# LAB03_2020-11-16_16-58-59.net
KiCad netlist of a schematic drawn in EasyEDA
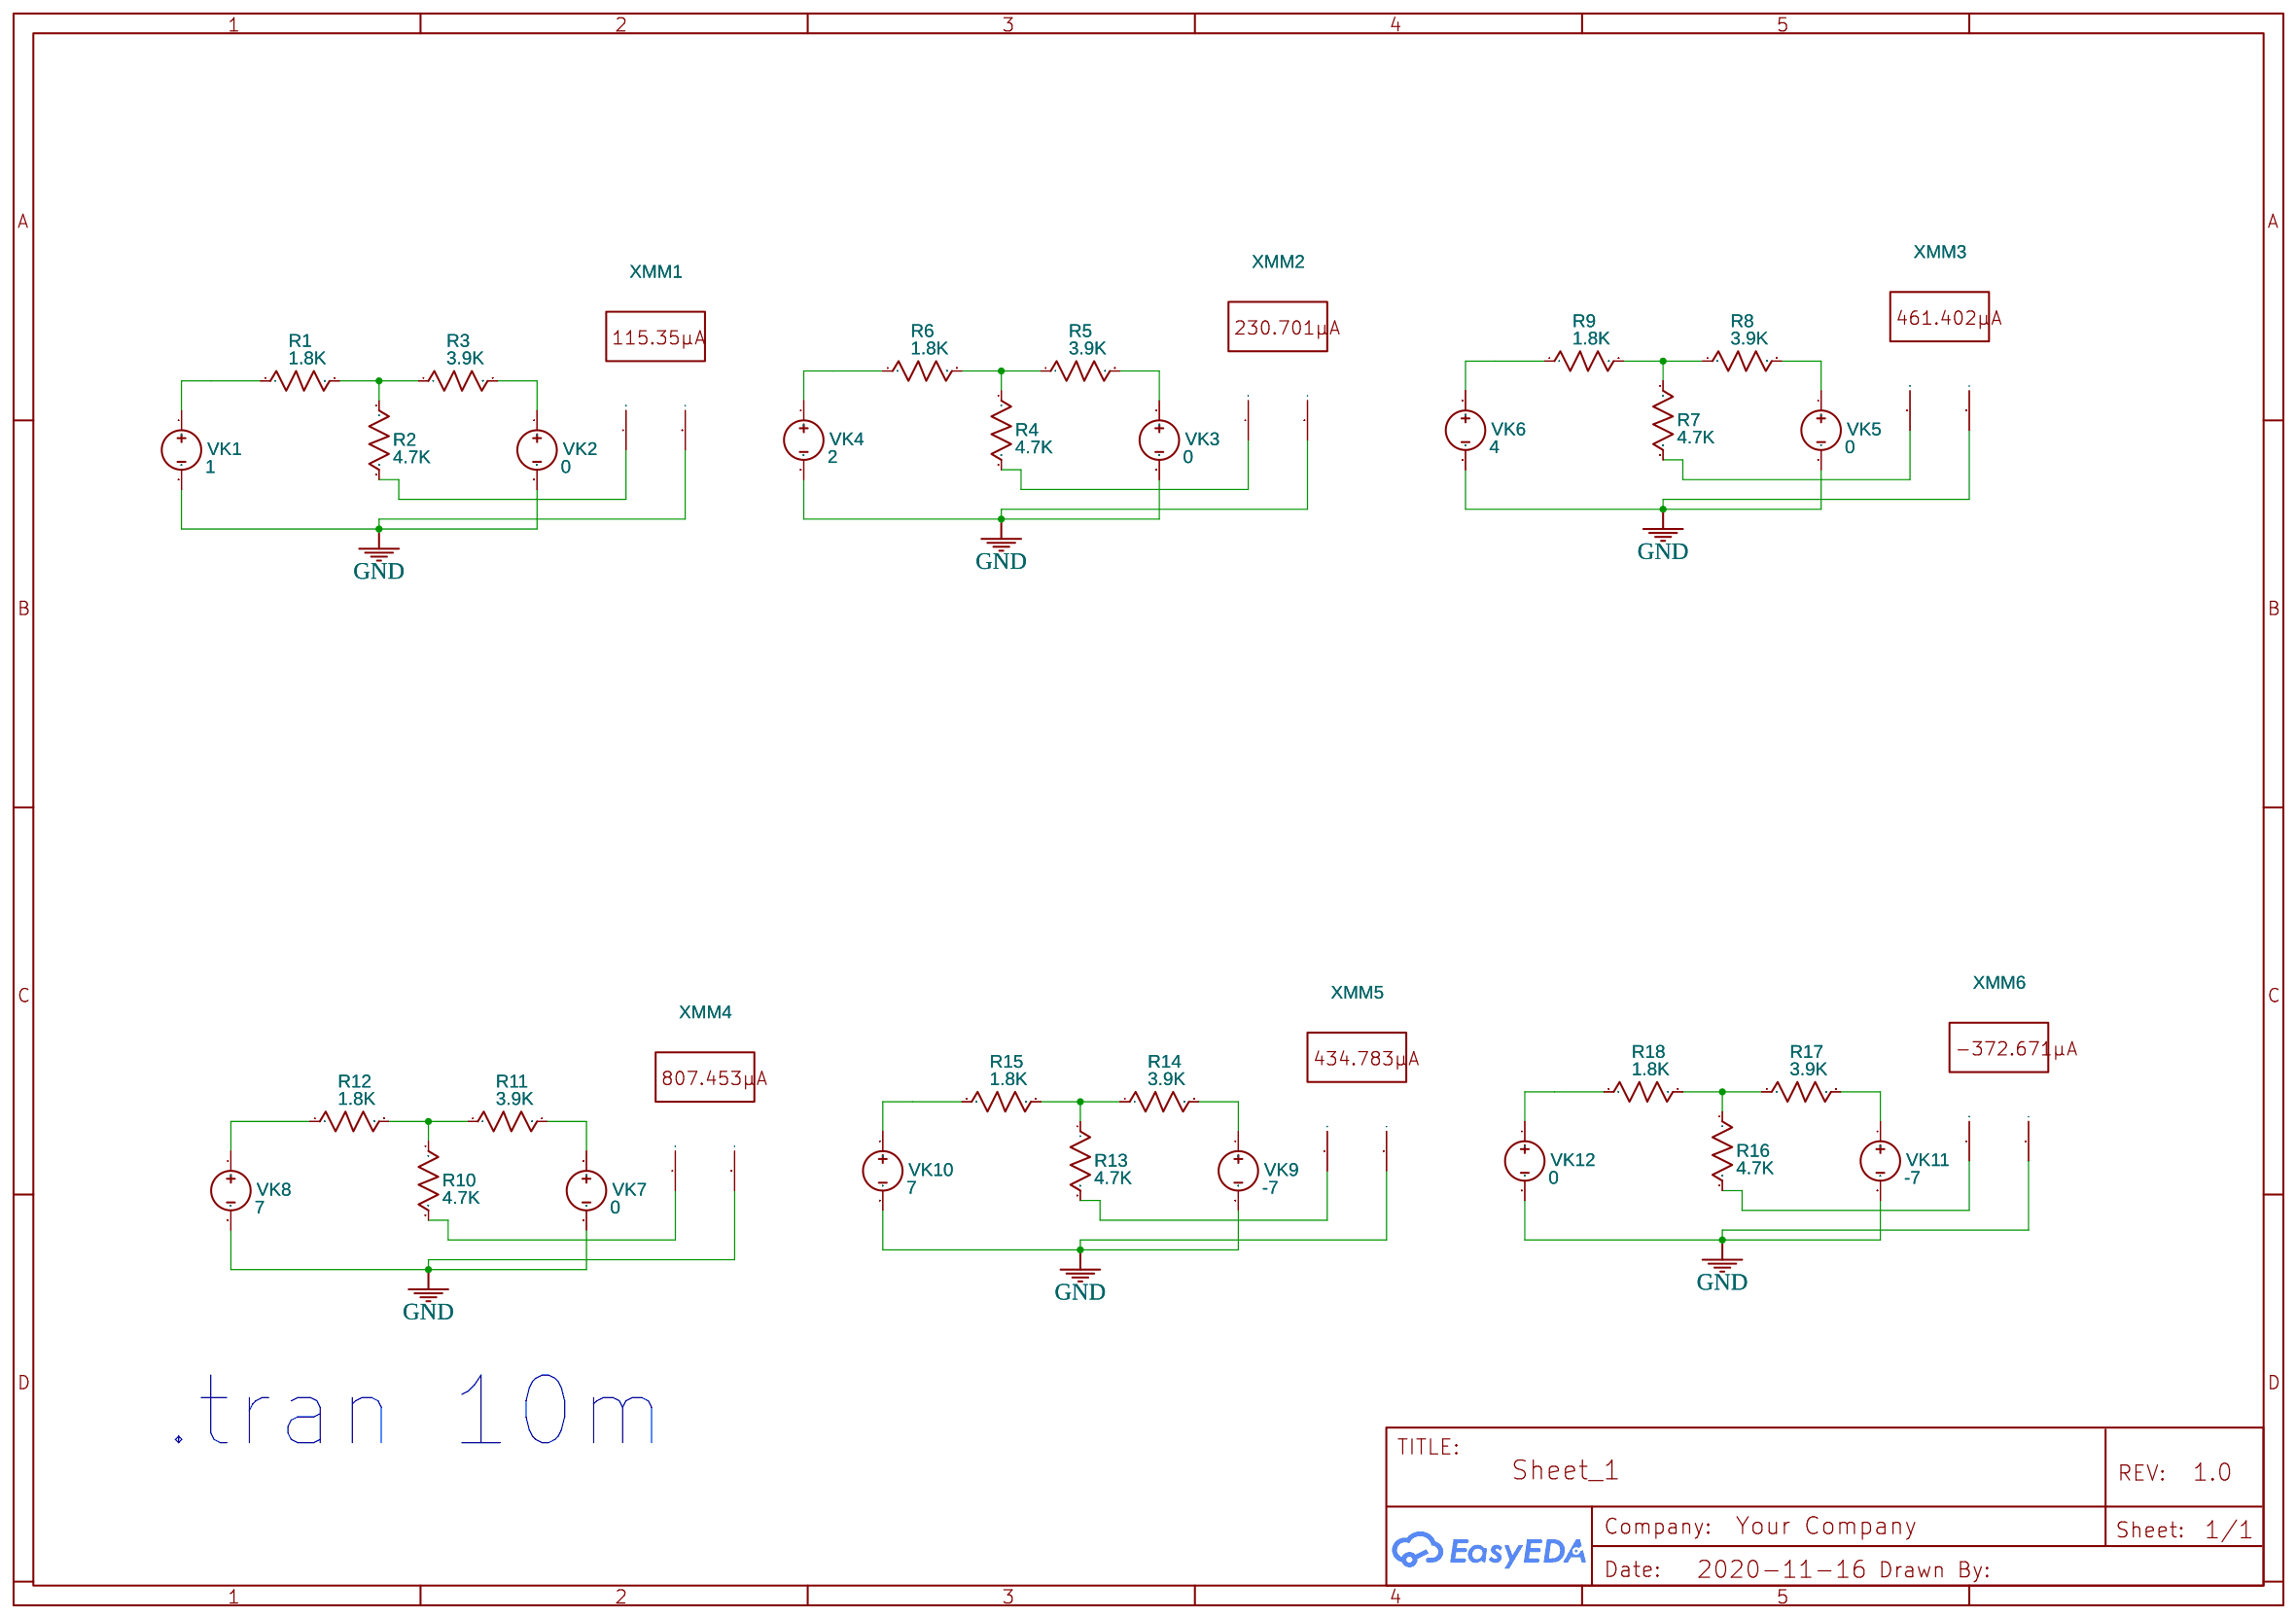
[diagram p0: schematic sheet]

(export (version "E")
  (design (tool "Eeschema 10.0.6"))
  (components
    (comp (ref "R1") (value "1.8K") (libsource (lib "") (part "Resistor_US_1")))
    (comp (ref "R2") (value "4.7K") (libsource (lib "") (part "Resistor_US")))
    (comp (ref "R3") (value "3.9K") (libsource (lib "") (part "Resistor_US_1")))
    (comp (ref "R4") (value "4.7K") (libsource (lib "") (part "Resistor_US")))
    (comp (ref "R5") (value "3.9K") (libsource (lib "") (part "Resistor_US_1")))
    (comp (ref "R6") (value "1.8K") (libsource (lib "") (part "Resistor_US_1")))
    (comp (ref "R7") (value "4.7K") (libsource (lib "") (part "Resistor_US")))
    (comp (ref "R8") (value "3.9K") (libsource (lib "") (part "Resistor_US_1")))
    (comp (ref "R9") (value "1.8K") (libsource (lib "") (part "Resistor_US_1")))
    (comp (ref "R10") (value "4.7K") (libsource (lib "") (part "Resistor_US")))
    (comp (ref "R11") (value "3.9K") (libsource (lib "") (part "Resistor_US_1")))
    (comp (ref "R12") (value "1.8K") (libsource (lib "") (part "Resistor_US_1")))
    (comp (ref "R13") (value "4.7K") (libsource (lib "") (part "Resistor_US")))
    (comp (ref "R14") (value "3.9K") (libsource (lib "") (part "Resistor_US_1")))
    (comp (ref "R15") (value "1.8K") (libsource (lib "") (part "Resistor_US_1")))
    (comp (ref "R16") (value "4.7K") (libsource (lib "") (part "Resistor_US")))
    (comp (ref "R17") (value "3.9K") (libsource (lib "") (part "Resistor_US_1")))
    (comp (ref "R18") (value "1.8K") (libsource (lib "") (part "Resistor_US_1")))
    (comp (ref "VK1") (value "1") (libsource (lib "") (part "VDC")))
    (comp (ref "VK2") (value "0") (libsource (lib "") (part "VDC")))
    (comp (ref "VK3") (value "0") (libsource (lib "") (part "VDC")))
    (comp (ref "VK4") (value "2") (libsource (lib "") (part "VDC")))
    (comp (ref "VK5") (value "0") (libsource (lib "") (part "VDC")))
    (comp (ref "VK6") (value "4") (libsource (lib "") (part "VDC")))
    (comp (ref "VK7") (value "0") (libsource (lib "") (part "VDC")))
    (comp (ref "VK8") (value "7") (libsource (lib "") (part "VDC")))
    (comp (ref "VK9") (value "-7") (libsource (lib "") (part "VDC")))
    (comp (ref "VK10") (value "7") (libsource (lib "") (part "VDC")))
    (comp (ref "VK11") (value "-7") (libsource (lib "") (part "VDC")))
    (comp (ref "VK12") (value "0") (libsource (lib "") (part "VDC")))
    (comp (ref "XMM1") (value "Multimeter") (libsource (lib "") (part "MULTIMETER_2")))
    (comp (ref "XMM2") (value "Multimeter") (libsource (lib "") (part "MULTIMETER_5")))
    (comp (ref "XMM3") (value "Multimeter") (libsource (lib "") (part "MULTIMETER_1")))
    (comp (ref "XMM4") (value "Multimeter") (libsource (lib "") (part "MULTIMETER_3")))
    (comp (ref "XMM5") (value "Multimeter") (libsource (lib "") (part "MULTIMETER")))
    (comp (ref "XMM6") (value "Multimeter") (libsource (lib "") (part "MULTIMETER_4")))
  )
  (nets
    (net (code "1") (name "GND") (class "Default")
      (node (ref "VK1") (pin "2") (pinfunction "2_2") (pintype "unspecified"))
      (node (ref "VK10") (pin "2") (pinfunction "2_2") (pintype "unspecified"))
      (node (ref "VK11") (pin "2") (pinfunction "2_2") (pintype "unspecified"))
      (node (ref "VK12") (pin "2") (pinfunction "2_2") (pintype "unspecified"))
      (node (ref "VK2") (pin "2") (pinfunction "2_2") (pintype "unspecified"))
      (node (ref "VK3") (pin "2") (pinfunction "2_2") (pintype "unspecified"))
      (node (ref "VK4") (pin "2") (pinfunction "2_2") (pintype "unspecified"))
      (node (ref "VK5") (pin "2") (pinfunction "2_2") (pintype "unspecified"))
      (node (ref "VK6") (pin "2") (pinfunction "2_2") (pintype "unspecified"))
      (node (ref "VK7") (pin "2") (pinfunction "2_2") (pintype "unspecified"))
      (node (ref "VK8") (pin "2") (pinfunction "2_2") (pintype "unspecified"))
      (node (ref "VK9") (pin "2") (pinfunction "2_2") (pintype "unspecified"))
      (node (ref "XMM1") (pin "2") (pinfunction "I_2") (pintype "unspecified"))
      (node (ref "XMM2") (pin "2") (pinfunction "I_2") (pintype "unspecified"))
      (node (ref "XMM3") (pin "2") (pinfunction "I_2") (pintype "unspecified"))
      (node (ref "XMM4") (pin "2") (pinfunction "I_2") (pintype "unspecified"))
      (node (ref "XMM5") (pin "2") (pinfunction "I_2") (pintype "unspecified"))
      (node (ref "XMM6") (pin "2") (pinfunction "I_2") (pintype "unspecified"))
    )
    (net (code "2") (name "Net-(R1-Pad1)") (class "Default")
      (node (ref "R1") (pin "1") (pinfunction "1_1") (pintype "unspecified"))
      (node (ref "VK1") (pin "1") (pinfunction "1_1") (pintype "unspecified"))
    )
    (net (code "3") (name "Net-(R1-Pad2)") (class "Default")
      (node (ref "R1") (pin "2") (pinfunction "2_2") (pintype "unspecified"))
      (node (ref "R2") (pin "1") (pinfunction "1_1") (pintype "unspecified"))
      (node (ref "R3") (pin "1") (pinfunction "1_1") (pintype "unspecified"))
    )
    (net (code "4") (name "Net-(R3-Pad2)") (class "Default")
      (node (ref "R3") (pin "2") (pinfunction "2_2") (pintype "unspecified"))
      (node (ref "VK2") (pin "1") (pinfunction "1_1") (pintype "unspecified"))
    )
    (net (code "5") (name "Net-(R4-Pad1)") (class "Default")
      (node (ref "R4") (pin "1") (pinfunction "1_1") (pintype "unspecified"))
      (node (ref "R5") (pin "1") (pinfunction "1_1") (pintype "unspecified"))
      (node (ref "R6") (pin "2") (pinfunction "2_2") (pintype "unspecified"))
    )
    (net (code "6") (name "Net-(R5-Pad2)") (class "Default")
      (node (ref "R5") (pin "2") (pinfunction "2_2") (pintype "unspecified"))
      (node (ref "VK3") (pin "1") (pinfunction "1_1") (pintype "unspecified"))
    )
    (net (code "7") (name "Net-(R6-Pad1)") (class "Default")
      (node (ref "R6") (pin "1") (pinfunction "1_1") (pintype "unspecified"))
      (node (ref "VK4") (pin "1") (pinfunction "1_1") (pintype "unspecified"))
    )
    (net (code "8") (name "Net-(R7-Pad1)") (class "Default")
      (node (ref "R7") (pin "1") (pinfunction "1_1") (pintype "unspecified"))
      (node (ref "R8") (pin "1") (pinfunction "1_1") (pintype "unspecified"))
      (node (ref "R9") (pin "2") (pinfunction "2_2") (pintype "unspecified"))
    )
    (net (code "9") (name "Net-(R8-Pad2)") (class "Default")
      (node (ref "R8") (pin "2") (pinfunction "2_2") (pintype "unspecified"))
      (node (ref "VK5") (pin "1") (pinfunction "1_1") (pintype "unspecified"))
    )
    (net (code "10") (name "Net-(R9-Pad1)") (class "Default")
      (node (ref "R9") (pin "1") (pinfunction "1_1") (pintype "unspecified"))
      (node (ref "VK6") (pin "1") (pinfunction "1_1") (pintype "unspecified"))
    )
    (net (code "11") (name "Net-(R10-Pad1)") (class "Default")
      (node (ref "R10") (pin "1") (pinfunction "1_1") (pintype "unspecified"))
      (node (ref "R11") (pin "1") (pinfunction "1_1") (pintype "unspecified"))
      (node (ref "R12") (pin "2") (pinfunction "2_2") (pintype "unspecified"))
    )
    (net (code "12") (name "Net-(R11-Pad2)") (class "Default")
      (node (ref "R11") (pin "2") (pinfunction "2_2") (pintype "unspecified"))
      (node (ref "VK7") (pin "1") (pinfunction "1_1") (pintype "unspecified"))
    )
    (net (code "13") (name "Net-(R12-Pad1)") (class "Default")
      (node (ref "R12") (pin "1") (pinfunction "1_1") (pintype "unspecified"))
      (node (ref "VK8") (pin "1") (pinfunction "1_1") (pintype "unspecified"))
    )
    (net (code "14") (name "Net-(R13-Pad1)") (class "Default")
      (node (ref "R13") (pin "1") (pinfunction "1_1") (pintype "unspecified"))
      (node (ref "R14") (pin "1") (pinfunction "1_1") (pintype "unspecified"))
      (node (ref "R15") (pin "2") (pinfunction "2_2") (pintype "unspecified"))
    )
    (net (code "15") (name "Net-(R14-Pad2)") (class "Default")
      (node (ref "R14") (pin "2") (pinfunction "2_2") (pintype "unspecified"))
      (node (ref "VK9") (pin "1") (pinfunction "1_1") (pintype "unspecified"))
    )
    (net (code "16") (name "Net-(R15-Pad1)") (class "Default")
      (node (ref "R15") (pin "1") (pinfunction "1_1") (pintype "unspecified"))
      (node (ref "VK10") (pin "1") (pinfunction "1_1") (pintype "unspecified"))
    )
    (net (code "17") (name "Net-(R16-Pad1)") (class "Default")
      (node (ref "R16") (pin "1") (pinfunction "1_1") (pintype "unspecified"))
      (node (ref "R17") (pin "1") (pinfunction "1_1") (pintype "unspecified"))
      (node (ref "R18") (pin "2") (pinfunction "2_2") (pintype "unspecified"))
    )
    (net (code "18") (name "Net-(R17-Pad2)") (class "Default")
      (node (ref "R17") (pin "2") (pinfunction "2_2") (pintype "unspecified"))
      (node (ref "VK11") (pin "1") (pinfunction "1_1") (pintype "unspecified"))
    )
    (net (code "19") (name "Net-(R18-Pad1)") (class "Default")
      (node (ref "R18") (pin "1") (pinfunction "1_1") (pintype "unspecified"))
      (node (ref "VK12") (pin "1") (pinfunction "1_1") (pintype "unspecified"))
    )
    (net (code "20") (name "Net-(XMM1-+)") (class "Default")
      (node (ref "R2") (pin "2") (pinfunction "2_2") (pintype "unspecified"))
      (node (ref "XMM1") (pin "1") (pinfunction "+_1") (pintype "unspecified"))
    )
    (net (code "21") (name "Net-(XMM2-+)") (class "Default")
      (node (ref "R4") (pin "2") (pinfunction "2_2") (pintype "unspecified"))
      (node (ref "XMM2") (pin "1") (pinfunction "+_1") (pintype "unspecified"))
    )
    (net (code "22") (name "Net-(XMM3-+)") (class "Default")
      (node (ref "R7") (pin "2") (pinfunction "2_2") (pintype "unspecified"))
      (node (ref "XMM3") (pin "1") (pinfunction "+_1") (pintype "unspecified"))
    )
    (net (code "23") (name "Net-(XMM4-+)") (class "Default")
      (node (ref "R10") (pin "2") (pinfunction "2_2") (pintype "unspecified"))
      (node (ref "XMM4") (pin "1") (pinfunction "+_1") (pintype "unspecified"))
    )
    (net (code "24") (name "Net-(XMM5-+)") (class "Default")
      (node (ref "R13") (pin "2") (pinfunction "2_2") (pintype "unspecified"))
      (node (ref "XMM5") (pin "1") (pinfunction "+_1") (pintype "unspecified"))
    )
    (net (code "25") (name "Net-(XMM6-+)") (class "Default")
      (node (ref "R16") (pin "2") (pinfunction "2_2") (pintype "unspecified"))
      (node (ref "XMM6") (pin "1") (pinfunction "+_1") (pintype "unspecified"))
    )
  )
)
